# PowerIsolation.net
KiCad netlist of a schematic drawn in Altium Designer
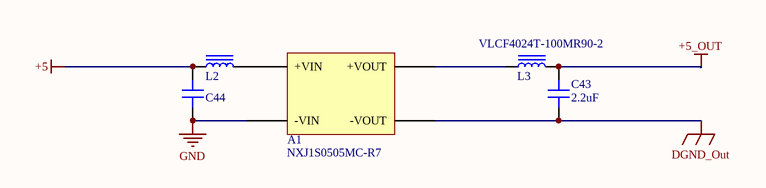
[diagram p0: PowerIsolation.SchDoc]

(export (version "E")
  (design (tool "Eeschema 10.0.6"))
  (components
    (comp (ref "A1")
      (value "NXJ1S0505MC-R7")
      (footprint "MURATA NXJ1")
      (description "DC/DC SM 1W 5V-5V SINGLE 4.2KV")
      (fields (field (name "MANUFACTURER") "Murata Power Solutions Inc."))
      (libsource (lib "Celestial Library Database") (part "MURATA NXJ1"))
    )
    (comp (ref "C43")
      (value "2.2uF")
      (footprint "CAP 1206/3216")
      (description "CAP CER 2.2UF 100V X7R 1206")
      (fields
        (field (name "PART NUMBER") "CL31B225KCHSNNE")
        (field (name "MANUFACTURER") "Samsung Electro-Mechanics America, Inc.")
      )
      (libsource (lib "Celestial Library Database") (part "Capacitor"))
    )
    (comp (ref "C44")
      (value "4.7uF")
      (footprint "CAP 1206/3216 - 1.8MM")
      (description "CAP CER 4.7UF 10V X7R 1206")
      (fields
        (field (name "PART NUMBER") "CL31B475KPHNNNE")
        (field (name "MANUFACTURER") "Samsung Electro-Mechanics America, Inc.")
      )
      (libsource (lib "Celestial Library Database") (part "Capacitor"))
    )
    (comp (ref "L2")
      (value "VLCF4024T-4R7N1R4-2")
      (footprint "TDK VLCF4024-2")
      (description "FIXED IND 4.7UH 1.43A 87 MOHM")
      (fields (field (name "MANUFACTURER") "TDK Corporation") (field (name "TOLERANCE") "30%"))
      (libsource (lib "Celestial Library Database") (part "Inductor"))
    )
    (comp (ref "L3")
      (value "VLCF4024T-100MR90-2")
      (footprint "TDK VLCF4024-2")
      (description "FIXED IND 10UH 900MA 136 MOHM")
      (fields (field (name "MANUFACTURER") "TDK Corporation") (field (name "TOLERANCE") "20%"))
      (libsource (lib "Celestial Library Database") (part "Inductor"))
    )
  )
  (nets
    (net (code "1") (name "+5") (class "Default")
      (node (ref "C44") (pin "2") (pinfunction "2_2") (pintype "passive"))
      (node (ref "L2") (pin "1") (pinfunction "1_1") (pintype "passive"))
    )
    (net (code "2") (name "+5_OUT") (class "Default")
      (node (ref "C43") (pin "1") (pinfunction "1_1") (pintype "passive"))
      (node (ref "L3") (pin "2") (pinfunction "2_2") (pintype "passive"))
    )
    (net (code "3") (name "DGND_Out") (class "Default")
      (node (ref "A1") (pin "7") (pinfunction "-VOUT_7") (pintype "passive"))
      (node (ref "C43") (pin "2") (pinfunction "2_2") (pintype "passive"))
    )
    (net (code "4") (name "GND") (class "Default")
      (node (ref "A1") (pin "1") (pinfunction "-VIN_1") (pintype "passive"))
      (node (ref "C44") (pin "1") (pinfunction "1_1") (pintype "passive"))
    )
    (net (code "5") (name "Net-(A1-+VIN)") (class "Default")
      (node (ref "A1") (pin "3") (pinfunction "+VIN_3") (pintype "passive"))
      (node (ref "L2") (pin "2") (pinfunction "2_2") (pintype "passive"))
    )
    (net (code "6") (name "Net-(A1-+VOUT)") (class "Default")
      (node (ref "A1") (pin "8") (pinfunction "+VOUT_8") (pintype "passive"))
      (node (ref "L3") (pin "1") (pinfunction "1_1") (pintype "passive"))
    )
  )
)
